# 7_-_Microcontroller.net
KiCad netlist of a schematic drawn in Altium Designer
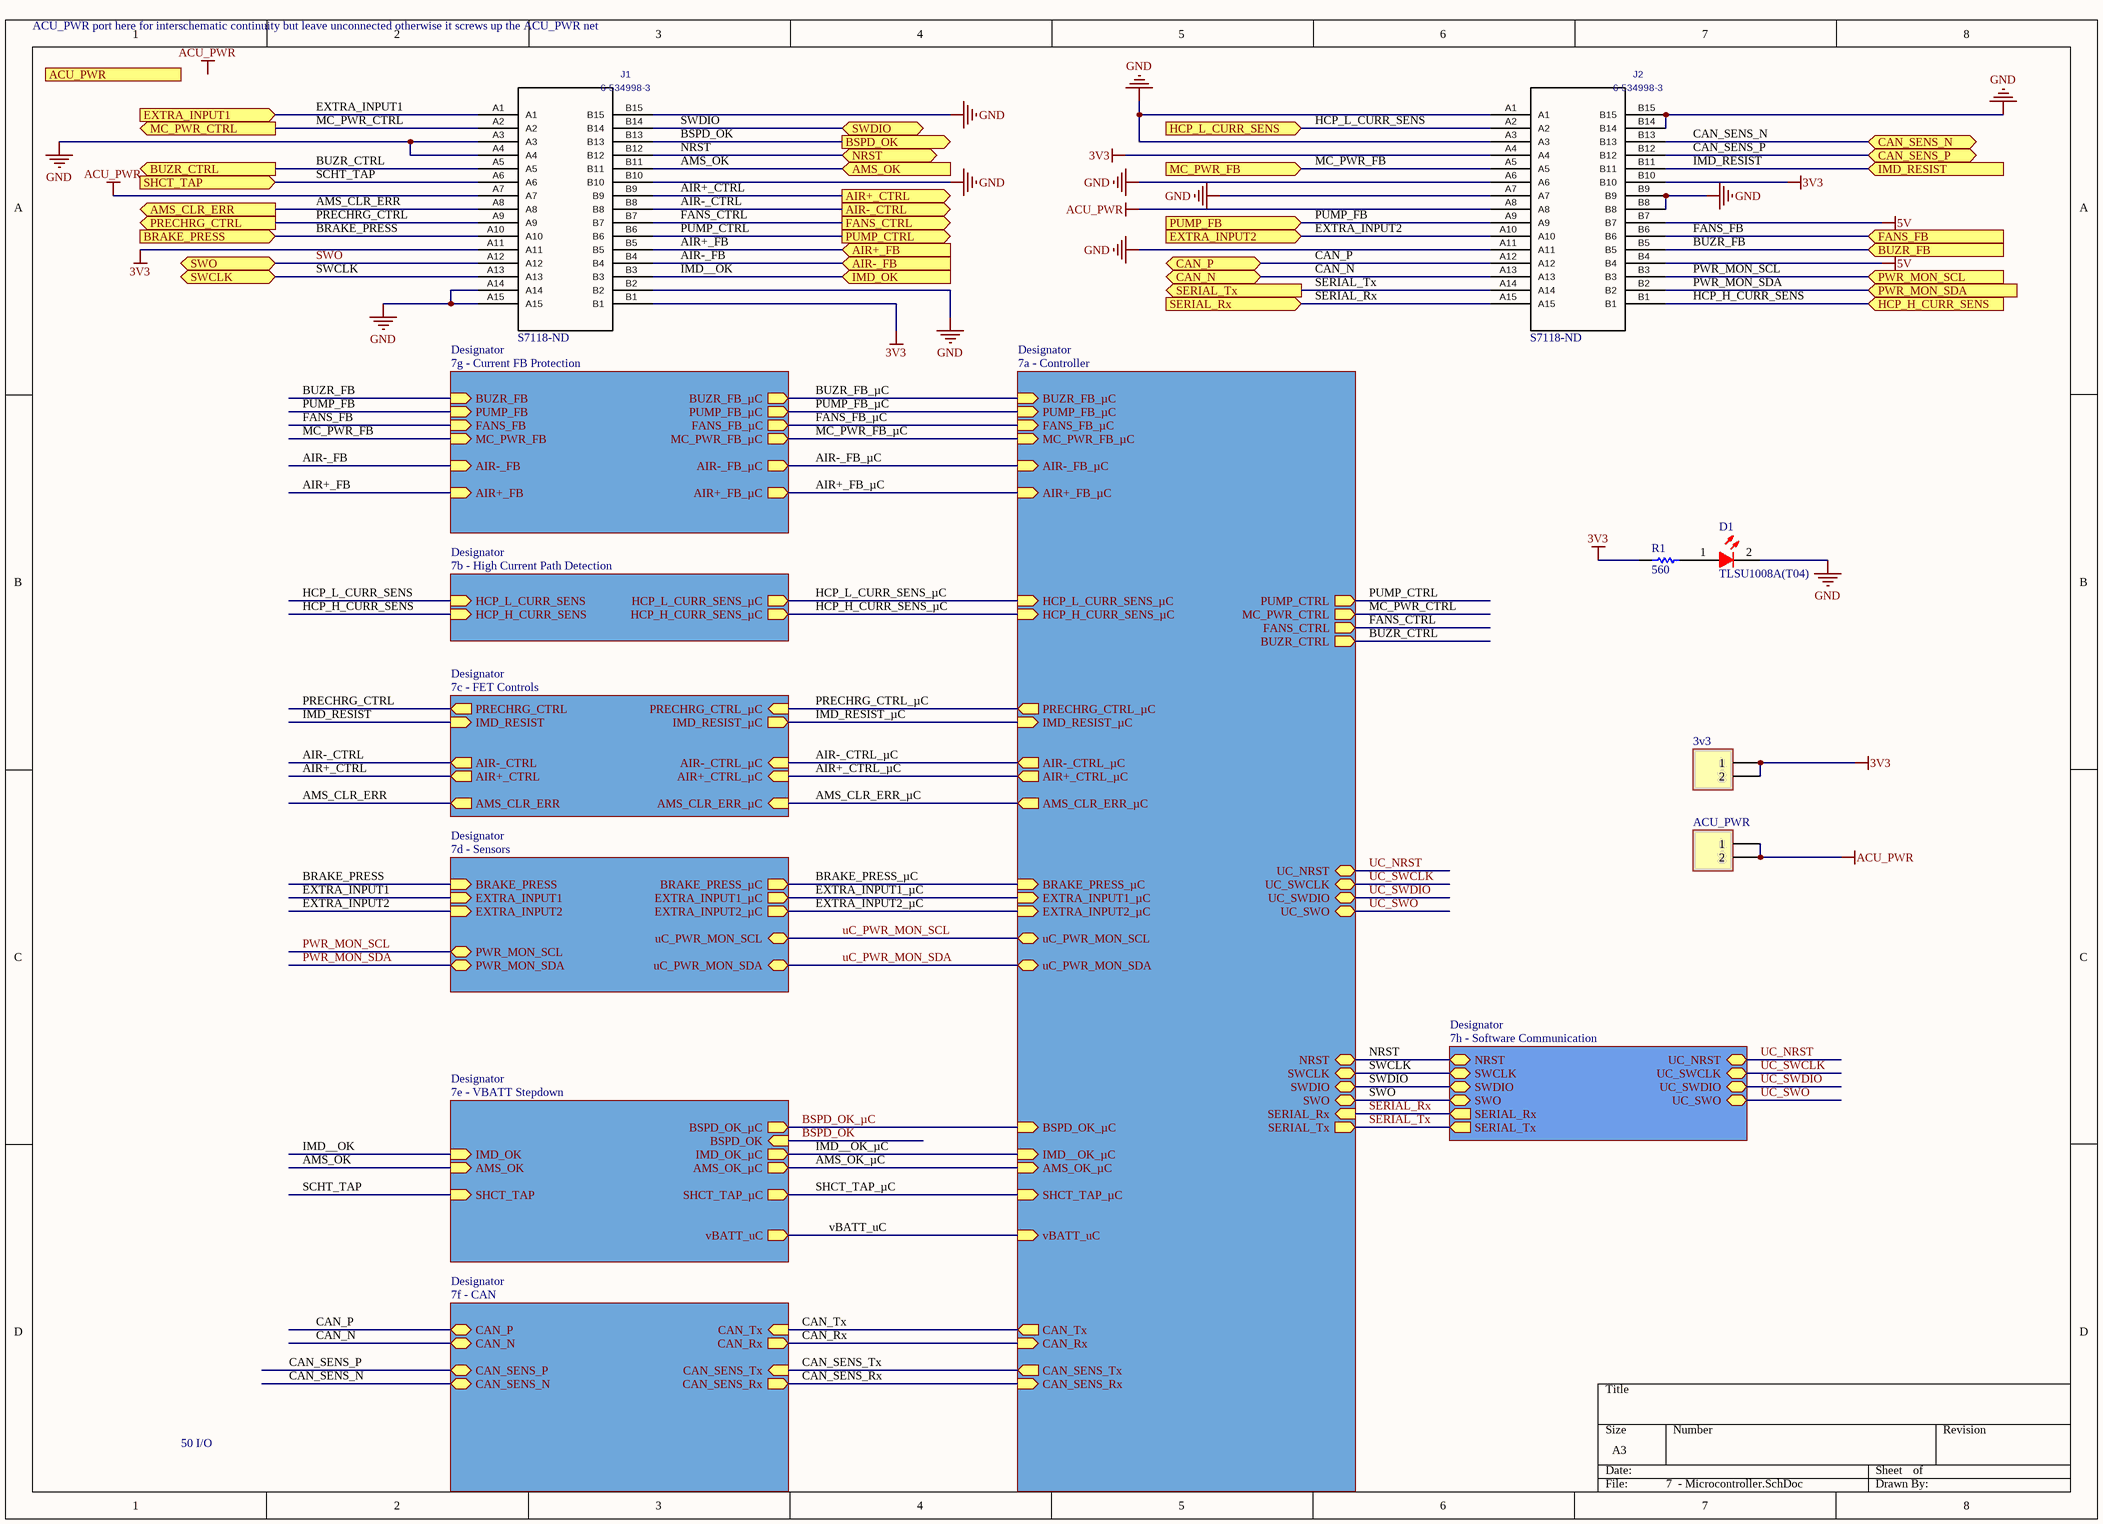
[diagram p0: 7  - Microcontroller.SchDoc]

(export (version "E")
  (design (tool "Eeschema 10.0.6"))
  (components
    (comp (ref "3v3")
      (value "~")
      (footprint "HDR1X2")
      (description "Header, 2-Pin")
      (fields (field (name "PUBLISHER") "Altium Limited"))
      (libsource (lib "Miscellaneous Connectors") (part "Header 2"))
    )
    (comp (ref "ACU_PWR")
      (value "~")
      (footprint "HDR1X2")
      (description "Header, 2-Pin")
      (fields (field (name "PUBLISHER") "Altium Limited"))
      (libsource (lib "Miscellaneous Connectors") (part "Header 2"))
    )
    (comp (ref "D1")
      (value "TLSU1008A(T04)")
      (footprint "TOSH-0603LED_RED_V")
      (description "LED, Red 0603 (1608) 63mCd")
      (fields (field (name "MANUFACTURER") "Toshiba"))
      (libsource (lib "Altium Content Vault") (part "TOSH-LED-RED-A1K2-2"))
    )
    (comp (ref "J1")
      (value "6-534998-3")
      (footprint "6-534998-5_6-534998-5(Primary)")
      (fields (field (name "SUPPLIER PART NUMBER 1") "S7118-ND"))
      (libsource (lib "ePBR22_ACU_Controller") (part "6-534998-3"))
    )
    (comp (ref "J2")
      (value "6-534998-3")
      (footprint "6-534998-5_6-534998-5(Primary)")
      (fields (field (name "SUPPLIER PART NUMBER 1") "S7118-ND"))
      (libsource (lib "ePBR22_ACU_Controller") (part "6-534998-3"))
    )
    (comp (ref "R1")
      (value "560")
      (footprint "RESC0603(1608)_L")
      (description "0603 (1608 Metric) Chip Resistor")
      (libsource (lib "Altium Content Vault") (part "RES_3"))
    )
  )
  (nets
    (net (code "1") (name "/AIR+_CTRL") (class "Default")
      (node (ref "J1") (pin "B9") (pinfunction "B9_B9") (pintype "passive"))
    )
    (net (code "3") (name "/AIR+_FB") (class "Default")
      (node (ref "J1") (pin "B5") (pinfunction "B5_B5") (pintype "passive"))
    )
    (net (code "5") (name "/AIR-_CTRL") (class "Default")
      (node (ref "J1") (pin "B8") (pinfunction "B8_B8") (pintype "passive"))
    )
    (net (code "7") (name "/AIR-_FB") (class "Default")
      (node (ref "J1") (pin "B4") (pinfunction "B4_B4") (pintype "passive"))
    )
    (net (code "9") (name "/AMS_CLR_ERR") (class "Default")
      (node (ref "J1") (pin "A8") (pinfunction "A8_A8") (pintype "passive"))
    )
    (net (code "11") (name "/AMS_OK") (class "Default")
      (node (ref "J1") (pin "B11") (pinfunction "B11_B11") (pintype "passive"))
    )
    (net (code "13") (name "/BRAKE_PRESS") (class "Default")
      (node (ref "J1") (pin "A10") (pinfunction "A10_A10") (pintype "passive"))
    )
    (net (code "15") (name "/BSPD_OK") (class "Default")
      (node (ref "J1") (pin "B13") (pinfunction "B13_B13") (pintype "passive"))
    )
    (net (code "17") (name "/BUZR_CTRL") (class "Default")
      (node (ref "J1") (pin "A5") (pinfunction "A5_A5") (pintype "passive"))
    )
    (net (code "18") (name "/BUZR_FB") (class "Default")
      (node (ref "J2") (pin "B5") (pinfunction "B5_B5") (pintype "passive"))
    )
    (net (code "20") (name "/CAN_N") (class "Default")
      (node (ref "J2") (pin "A13") (pinfunction "A13_A13") (pintype "passive"))
    )
    (net (code "21") (name "/CAN_P") (class "Default")
      (node (ref "J2") (pin "A12") (pinfunction "A12_A12") (pintype "passive"))
    )
    (net (code "23") (name "/CAN_SENS_N") (class "Default")
      (node (ref "J2") (pin "B13") (pinfunction "B13_B13") (pintype "passive"))
    )
    (net (code "24") (name "/CAN_SENS_P") (class "Default")
      (node (ref "J2") (pin "B12") (pinfunction "B12_B12") (pintype "passive"))
    )
    (net (code "28") (name "/EXTRA_INPUT1") (class "Default")
      (node (ref "J1") (pin "A1") (pinfunction "A1_A1") (pintype "passive"))
    )
    (net (code "30") (name "/EXTRA_INPUT2") (class "Default")
      (node (ref "J2") (pin "A10") (pinfunction "A10_A10") (pintype "passive"))
    )
    (net (code "32") (name "/FANS_CTRL") (class "Default")
      (node (ref "J1") (pin "B7") (pinfunction "B7_B7") (pintype "passive"))
    )
    (net (code "33") (name "/FANS_FB") (class "Default")
      (node (ref "J2") (pin "B6") (pinfunction "B6_B6") (pintype "passive"))
    )
    (net (code "35") (name "/HCP_H_CURR_SENS") (class "Default")
      (node (ref "J2") (pin "B1") (pinfunction "B1_B1") (pintype "passive"))
    )
    (net (code "37") (name "/HCP_L_CURR_SENS") (class "Default")
      (node (ref "J2") (pin "A2") (pinfunction "A2_A2") (pintype "passive"))
    )
    (net (code "39") (name "/IMD_RESIST") (class "Default")
      (node (ref "J2") (pin "B11") (pinfunction "B11_B11") (pintype "passive"))
    )
    (net (code "41") (name "/IMD__OK") (class "Default")
      (node (ref "J1") (pin "B3") (pinfunction "B3_B3") (pintype "passive"))
    )
    (net (code "43") (name "/MC_PWR_CTRL") (class "Default")
      (node (ref "J1") (pin "A2") (pinfunction "A2_A2") (pintype "passive"))
    )
    (net (code "44") (name "/MC_PWR_FB") (class "Default")
      (node (ref "J2") (pin "A5") (pinfunction "A5_A5") (pintype "passive"))
    )
    (net (code "46") (name "/NRST") (class "Default")
      (node (ref "J1") (pin "B12") (pinfunction "B12_B12") (pintype "passive"))
    )
    (net (code "47") (name "/PRECHRG_CTRL") (class "Default")
      (node (ref "J1") (pin "A9") (pinfunction "A9_A9") (pintype "passive"))
    )
    (net (code "49") (name "/PUMP_CTRL") (class "Default")
      (node (ref "J1") (pin "B6") (pinfunction "B6_B6") (pintype "passive"))
    )
    (net (code "50") (name "/PUMP_FB") (class "Default")
      (node (ref "J2") (pin "A9") (pinfunction "A9_A9") (pintype "passive"))
    )
    (net (code "52") (name "/PWR_MON_SCL") (class "Default")
      (node (ref "J2") (pin "B3") (pinfunction "B3_B3") (pintype "passive"))
    )
    (net (code "53") (name "/PWR_MON_SDA") (class "Default")
      (node (ref "J2") (pin "B2") (pinfunction "B2_B2") (pintype "passive"))
    )
    (net (code "54") (name "/SCHT_TAP") (class "Default")
      (node (ref "J1") (pin "A6") (pinfunction "A6_A6") (pintype "passive"))
    )
    (net (code "55") (name "/SERIAL_Rx") (class "Default")
      (node (ref "J2") (pin "A15") (pinfunction "A15_A15") (pintype "passive"))
    )
    (net (code "56") (name "/SERIAL_Tx") (class "Default")
      (node (ref "J2") (pin "A14") (pinfunction "A14_A14") (pintype "passive"))
    )
    (net (code "58") (name "/SWCLK") (class "Default")
      (node (ref "J1") (pin "A13") (pinfunction "A13_A13") (pintype "passive"))
    )
    (net (code "59") (name "/SWDIO") (class "Default")
      (node (ref "J1") (pin "B14") (pinfunction "B14_B14") (pintype "passive"))
    )
    (net (code "60") (name "/SWO") (class "Default")
      (node (ref "J1") (pin "A12") (pinfunction "A12_A12") (pintype "passive"))
    )
    (net (code "68") (name "3V3") (class "Default")
      (node (ref "3v3") (pin "1") (pinfunction "1_1") (pintype "passive"))
      (node (ref "3v3") (pin "2") (pinfunction "2_2") (pintype "passive"))
      (node (ref "J1") (pin "A11") (pinfunction "A11_A11") (pintype "passive"))
      (node (ref "J1") (pin "B1") (pinfunction "B1_B1") (pintype "passive"))
      (node (ref "J2") (pin "A4") (pinfunction "A4_A4") (pintype "passive"))
      (node (ref "J2") (pin "B10") (pinfunction "B10_B10") (pintype "passive"))
      (node (ref "R1") (pin "1") (pinfunction "1_1") (pintype "passive"))
    )
    (net (code "69") (name "5V") (class "Default")
      (node (ref "J2") (pin "B4") (pinfunction "B4_B4") (pintype "passive"))
      (node (ref "J2") (pin "B7") (pinfunction "B7_B7") (pintype "passive"))
    )
    (net (code "70") (name "ACU_PWR") (class "Default")
      (node (ref "ACU_PWR") (pin "1") (pinfunction "1_1") (pintype "passive"))
      (node (ref "ACU_PWR") (pin "2") (pinfunction "2_2") (pintype "passive"))
      (node (ref "J1") (pin "A7") (pinfunction "A7_A7") (pintype "passive"))
      (node (ref "J2") (pin "A8") (pinfunction "A8_A8") (pintype "passive"))
    )
    (net (code "71") (name "GND") (class "Default")
      (node (ref "D1") (pin "2") (pinfunction "K_2") (pintype "passive"))
      (node (ref "J1") (pin "A14") (pinfunction "A14_A14") (pintype "passive"))
      (node (ref "J1") (pin "A15") (pinfunction "A15_A15") (pintype "passive"))
      (node (ref "J1") (pin "A3") (pinfunction "A3_A3") (pintype "passive"))
      (node (ref "J1") (pin "A4") (pinfunction "A4_A4") (pintype "passive"))
      (node (ref "J1") (pin "B10") (pinfunction "B10_B10") (pintype "passive"))
      (node (ref "J1") (pin "B15") (pinfunction "B15_B15") (pintype "passive"))
      (node (ref "J1") (pin "B2") (pinfunction "B2_B2") (pintype "passive"))
      (node (ref "J2") (pin "A1") (pinfunction "A1_A1") (pintype "passive"))
      (node (ref "J2") (pin "A11") (pinfunction "A11_A11") (pintype "passive"))
      (node (ref "J2") (pin "A3") (pinfunction "A3_A3") (pintype "passive"))
      (node (ref "J2") (pin "A6") (pinfunction "A6_A6") (pintype "passive"))
      (node (ref "J2") (pin "A7") (pinfunction "A7_A7") (pintype "passive"))
      (node (ref "J2") (pin "B14") (pinfunction "B14_B14") (pintype "passive"))
      (node (ref "J2") (pin "B15") (pinfunction "B15_B15") (pintype "passive"))
      (node (ref "J2") (pin "B8") (pinfunction "B8_B8") (pintype "passive"))
      (node (ref "J2") (pin "B9") (pinfunction "B9_B9") (pintype "passive"))
    )
    (net (code "72") (name "Net-(D1-A)") (class "Default")
      (node (ref "D1") (pin "1") (pinfunction "A_1") (pintype "passive"))
      (node (ref "R1") (pin "2") (pinfunction "2_2") (pintype "passive"))
    )
  )
)
